# 09-5V_Monitor.net
KiCad netlist of a schematic drawn in Altium Designer
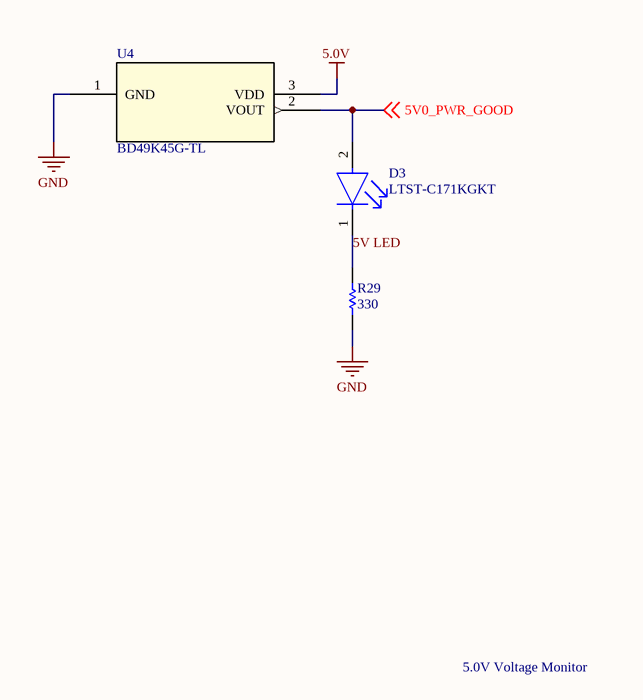
[diagram p0: 09-5V_Monitor.SchDoc]

(export (version "E")
  (design (tool "Eeschema 10.0.6"))
  (components
    (comp (ref "D3")
      (value "LTST-C171KGKT")
      (footprint "FP-LTST-C171KGKT-MFG")
      (description "LED GREEN CLEAR SMD")
      (libsource (lib "Altium Content Vault") (part "8706943c75ba83719d021d2fdc84c58"))
    )
    (comp (ref "R29")
      (value "330")
      (footprint "RES_0805")
      (description "RES 330 OHM 1% 1/8W 0805")
      (fields (field (name "TOLERANCE") "1%"))
      (libsource (lib "team6") (part "RES_0805_R_330.00"))
    )
    (comp (ref "U4")
      (value "BD49K45G-TL")
      (footprint "SSOP3_ROM")
      (description "No Description Available")
      (fields (field (name "COPYRIGHT") "Copyright (C) 2022 Ultra Librarian. All rights reserved."))
      (libsource (lib "team6") (part "BD49K45G-TL"))
    )
  )
  (nets
    (net (code "1") (name "/5V LED") (class "Default")
      (node (ref "D3") (pin "1") (pinfunction "C_1") (pintype "passive"))
      (node (ref "R29") (pin "2") (pinfunction "2_2") (pintype "passive"))
    )
    (net (code "2") (name "5.0V") (class "Default")
      (node (ref "U4") (pin "3") (pinfunction "VDD_3") (pintype "power_in"))
    )
    (net (code "3") (name "5V0_PWR_GOOD") (class "Default")
      (node (ref "D3") (pin "2") (pinfunction "A_2") (pintype "passive"))
      (node (ref "U4") (pin "2") (pinfunction "VOUT_2") (pintype "output"))
    )
    (net (code "4") (name "GND") (class "Default")
      (node (ref "R29") (pin "1") (pinfunction "1_1") (pintype "passive"))
      (node (ref "U4") (pin "1") (pinfunction "GND_1") (pintype "passive"))
    )
  )
)
